# ESenseFE-Dual-TwinT-60HzNotchFilter-AdjQ.net
KiCad netlist of a schematic drawn in Altium Designer
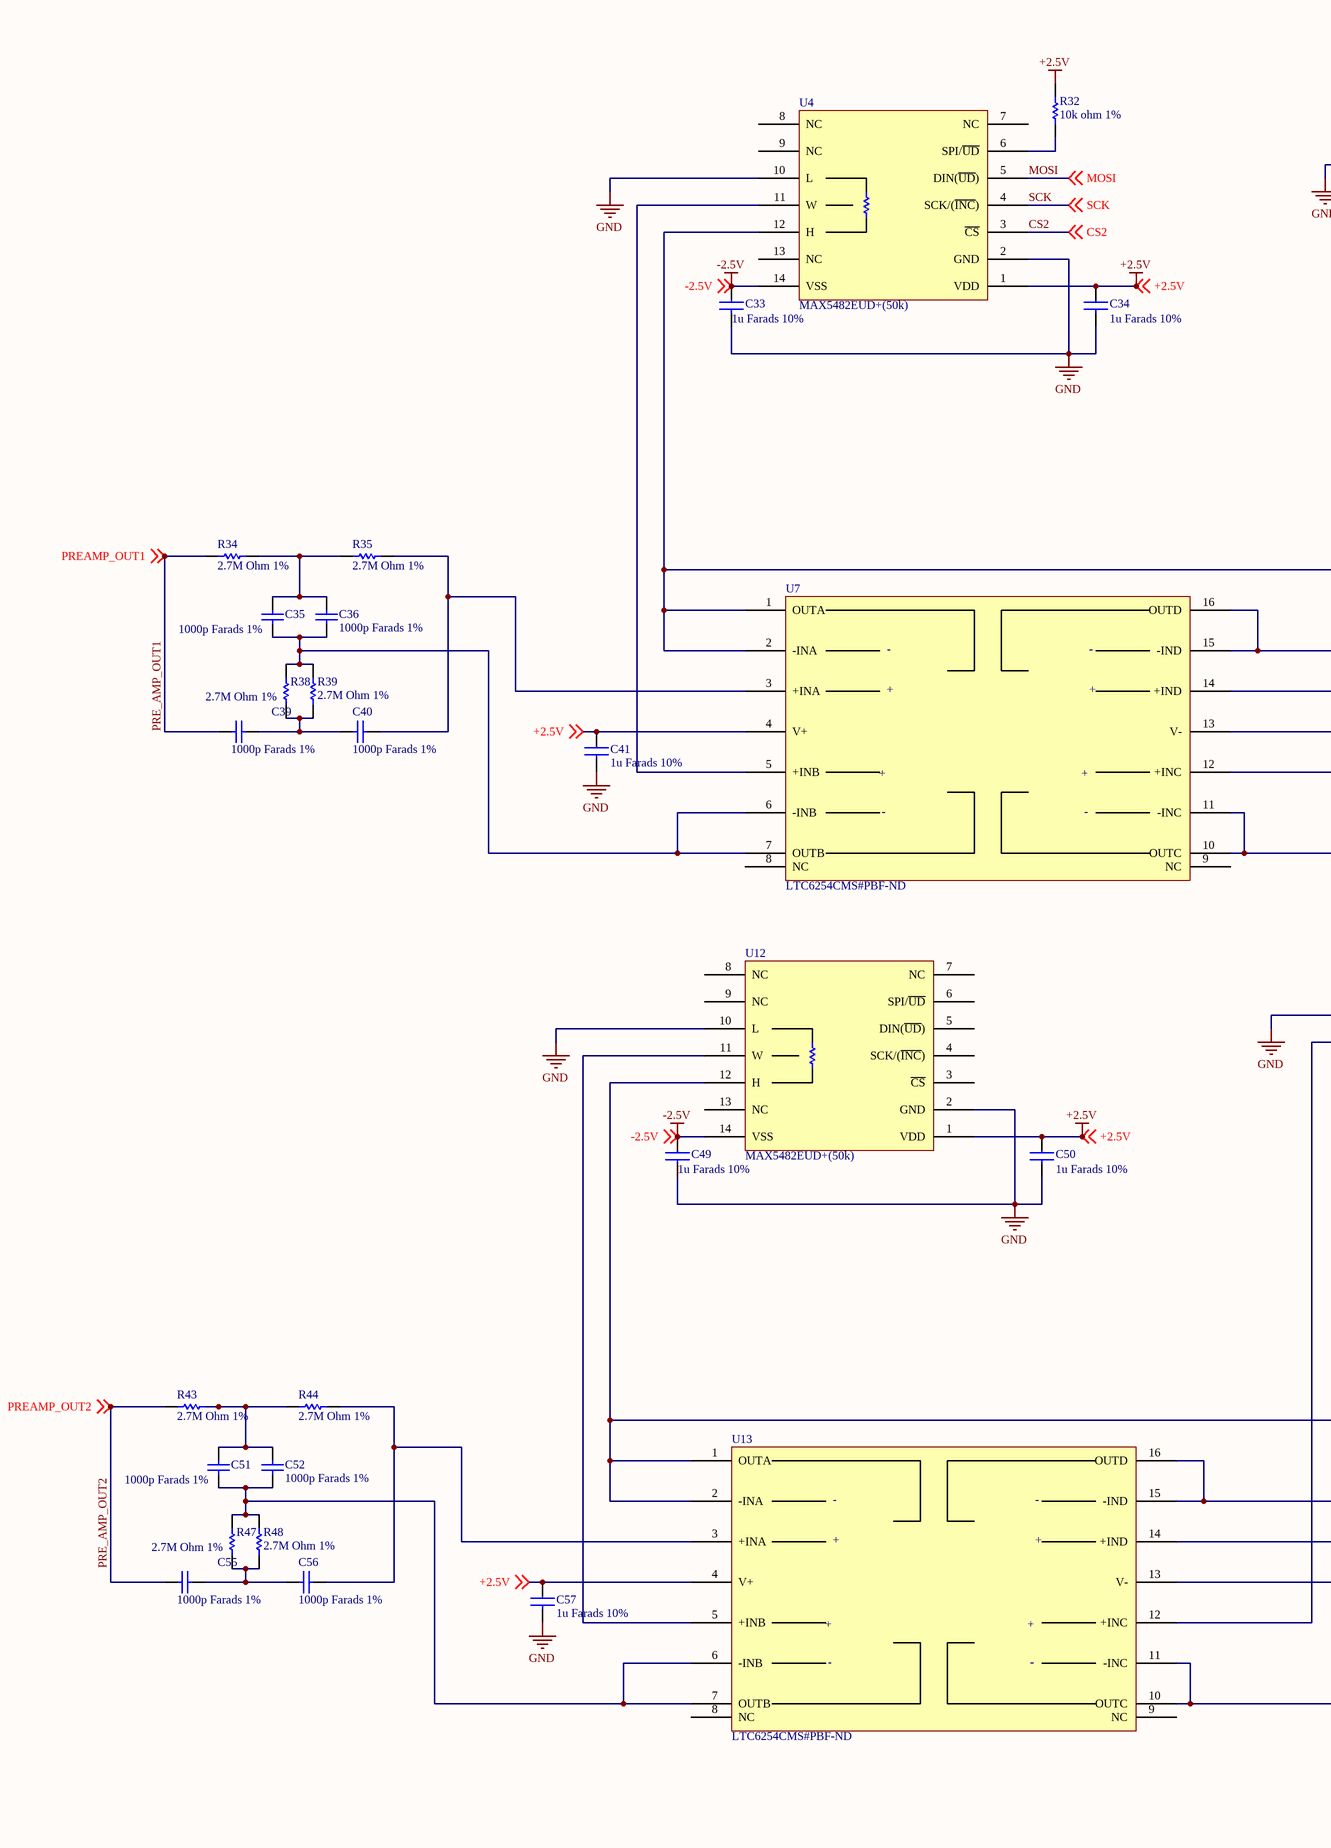
[diagram p0: ESenseFE-Dual-TwinT-60HzNotchFilter-AdjQ.SchDoc, left]
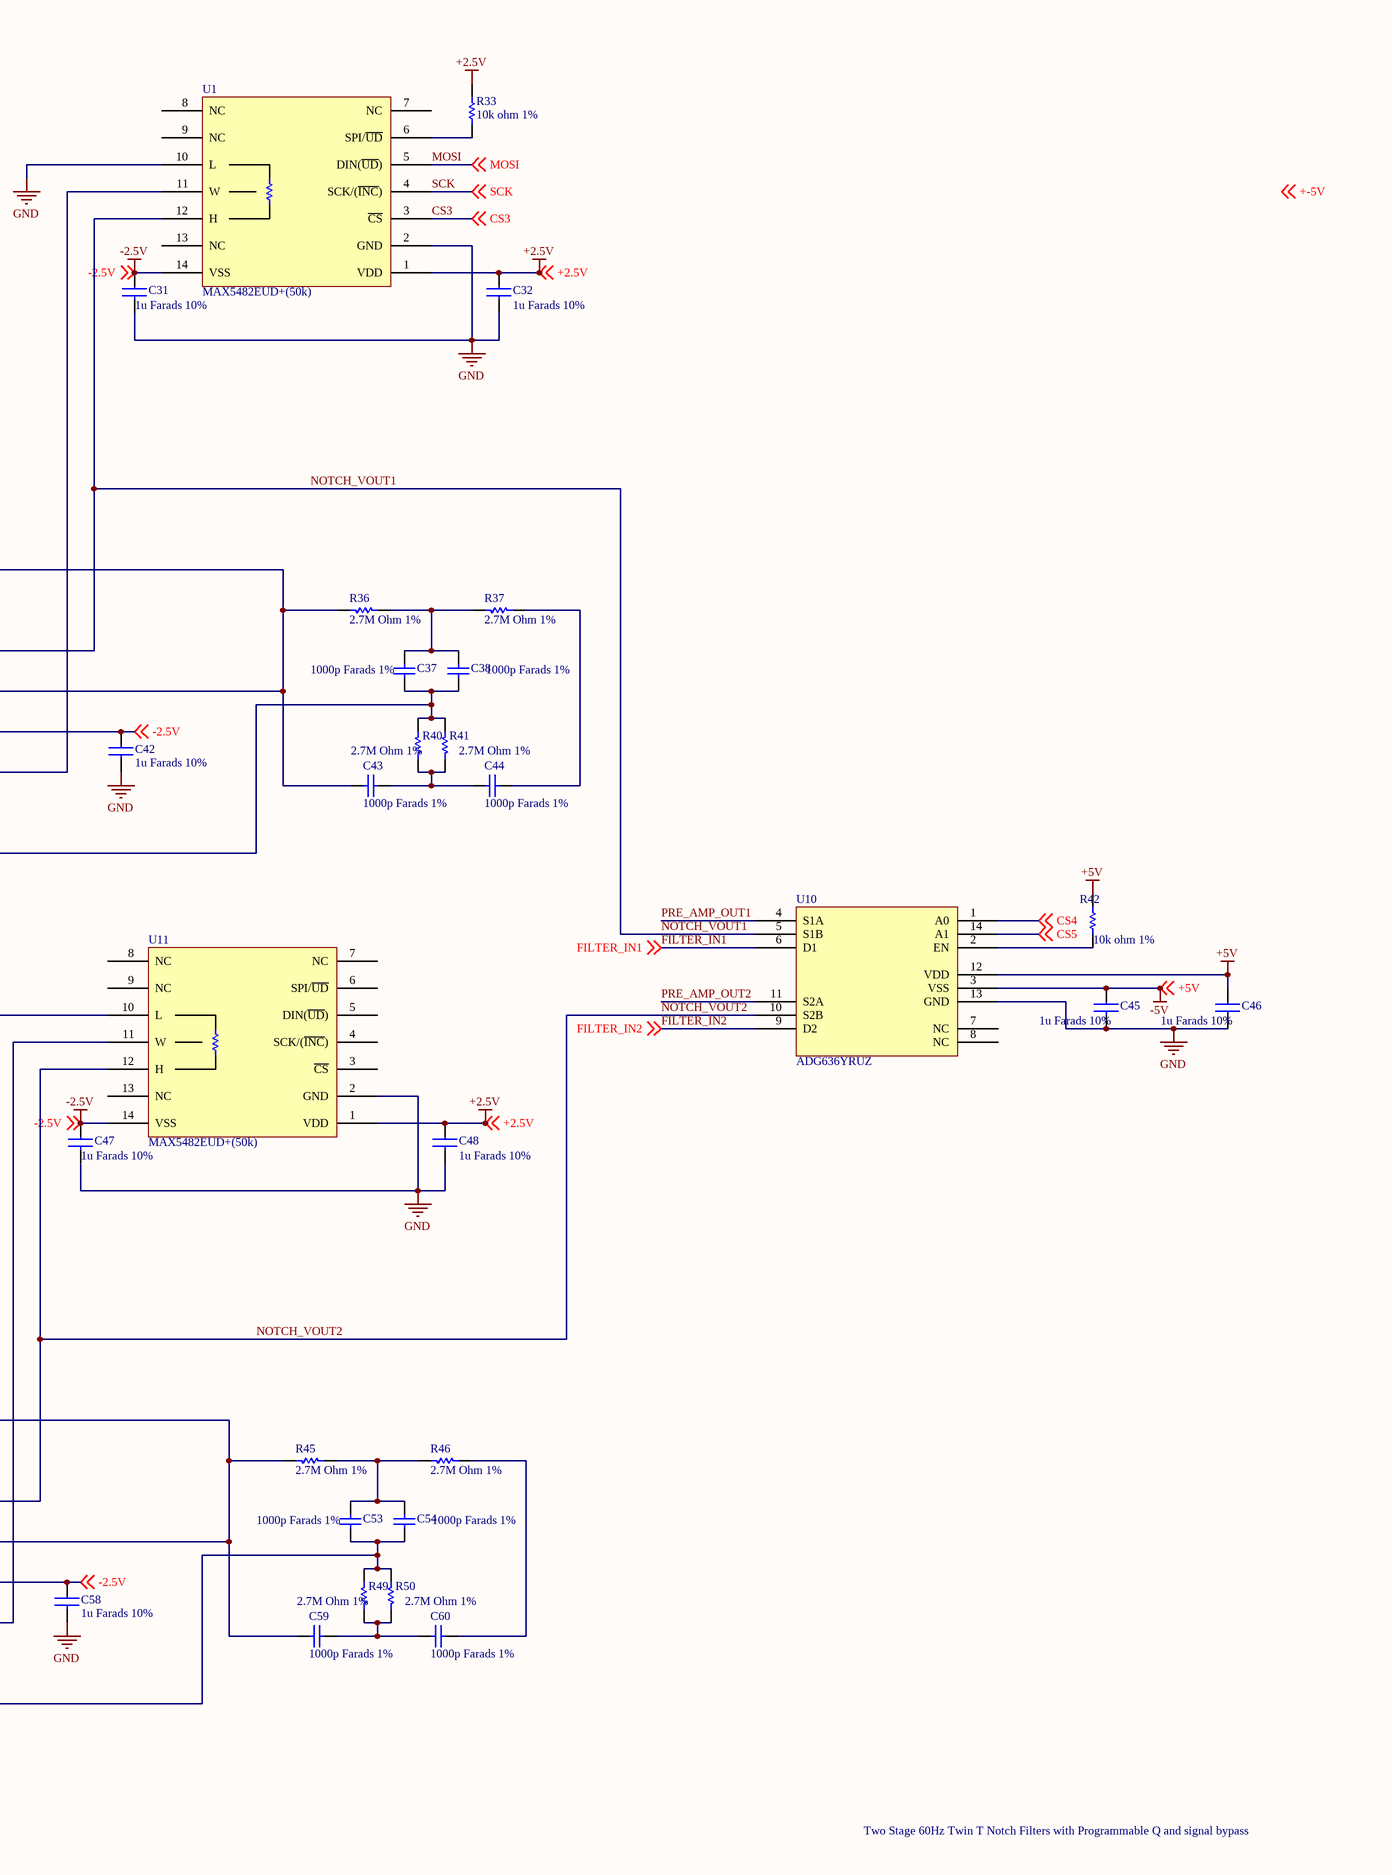
[diagram p1: ESenseFE-Dual-TwinT-60HzNotchFilter-AdjQ.SchDoc, right]

(export (version "E")
  (design (tool "Eeschema 10.0.6"))
  (components
    (comp (ref "C31")
      (value "1u Farads 10%")
      (footprint "SM/C_0603")
      (description "CAP CER 1.0UF 10V 10% X5R 0603")
      (fields (field (name "MFRPARTNUM") "GRM188R61A105KA61D"))
      (libsource (lib "FriedParts") (part "CAP NP"))
    )
    (comp (ref "C32")
      (value "1u Farads 10%")
      (footprint "SM/C_0603")
      (description "CAP CER 1.0UF 10V 10% X5R 0603")
      (fields (field (name "MFRPARTNUM") "GRM188R61A105KA61D"))
      (libsource (lib "FriedParts") (part "CAP NP"))
    )
    (comp (ref "C33")
      (value "1u Farads 10%")
      (footprint "SM/C_0603")
      (description "CAP CER 1.0UF 10V 10% X5R 0603")
      (fields (field (name "MFRPARTNUM") "GRM188R61A105KA61D"))
      (libsource (lib "FriedParts") (part "CAP NP"))
    )
    (comp (ref "C34")
      (value "1u Farads 10%")
      (footprint "SM/C_0603")
      (description "CAP CER 1.0UF 10V 10% X5R 0603")
      (fields (field (name "MFRPARTNUM") "GRM188R61A105KA61D"))
      (libsource (lib "FriedParts") (part "CAP NP"))
    )
    (comp (ref "C35")
      (value "1000p Farads 1%")
      (footprint "SM/C_0603")
      (description "capacitor ceramic 1000pf, 50v, c0g, 0603; dielectric")
      (fields (field (name "MFRPARTNUM") "06035A102FAT2A"))
      (libsource (lib "FriedParts") (part "CAP"))
    )
    (comp (ref "C36")
      (value "1000p Farads 1%")
      (footprint "SM/C_0603")
      (description "capacitor ceramic 1000pf, 50v, c0g, 0603; dielectric")
      (fields (field (name "MFRPARTNUM") "06035A102FAT2A"))
      (libsource (lib "FriedParts") (part "CAP"))
    )
    (comp (ref "C37")
      (value "1000p Farads 1%")
      (footprint "SM/C_0603")
      (description "capacitor ceramic 1000pf, 50v, c0g, 0603; dielectric")
      (fields (field (name "MFRPARTNUM") "06035A102FAT2A"))
      (libsource (lib "FriedParts") (part "CAP"))
    )
    (comp (ref "C38")
      (value "1000p Farads 1%")
      (footprint "SM/C_0603")
      (description "capacitor ceramic 1000pf, 50v, c0g, 0603; dielectric")
      (fields (field (name "MFRPARTNUM") "06035A102FAT2A"))
      (libsource (lib "FriedParts") (part "CAP"))
    )
    (comp (ref "C39")
      (value "1000p Farads 1%")
      (footprint "SM/C_0603")
      (description "capacitor ceramic 1000pf, 50v, c0g, 0603; dielectric")
      (fields (field (name "MFRPARTNUM") "06035A102FAT2A"))
      (libsource (lib "FriedParts") (part "CAP"))
    )
    (comp (ref "C40")
      (value "1000p Farads 1%")
      (footprint "SM/C_0603")
      (description "capacitor ceramic 1000pf, 50v, c0g, 0603; dielectric")
      (fields (field (name "MFRPARTNUM") "06035A102FAT2A"))
      (libsource (lib "FriedParts") (part "CAP"))
    )
    (comp (ref "C41")
      (value "1u Farads 10%")
      (footprint "SM/C_0603")
      (description "CAP CER 1.0UF 10V 10% X5R 0603")
      (fields (field (name "MFRPARTNUM") "GRM188R61A105KA61D"))
      (libsource (lib "FriedParts") (part "CAP NP"))
    )
    (comp (ref "C42")
      (value "1u Farads 10%")
      (footprint "SM/C_0603")
      (description "CAP CER 1.0UF 10V 10% X5R 0603")
      (fields (field (name "MFRPARTNUM") "GRM188R61A105KA61D"))
      (libsource (lib "FriedParts") (part "CAP NP"))
    )
    (comp (ref "C43")
      (value "1000p Farads 1%")
      (footprint "SM/C_0603")
      (description "capacitor ceramic 1000pf, 50v, c0g, 0603; dielectric")
      (fields (field (name "MFRPARTNUM") "06035A102FAT2A"))
      (libsource (lib "FriedParts") (part "CAP"))
    )
    (comp (ref "C44")
      (value "1000p Farads 1%")
      (footprint "SM/C_0603")
      (description "capacitor ceramic 1000pf, 50v, c0g, 0603; dielectric")
      (fields (field (name "MFRPARTNUM") "06035A102FAT2A"))
      (libsource (lib "FriedParts") (part "CAP"))
    )
    (comp (ref "C45")
      (value "1u Farads 10%")
      (footprint "SM/C_0603")
      (description "CAP CER 1.0UF 10V 10% X5R 0603")
      (fields (field (name "MFRPARTNUM") "GRM188R61A105KA61D"))
      (libsource (lib "FriedParts") (part "CAP NP"))
    )
    (comp (ref "C46")
      (value "1u Farads 10%")
      (footprint "SM/C_0603")
      (description "CAP CER 1.0UF 10V 10% X5R 0603")
      (fields (field (name "MFRPARTNUM") "GRM188R61A105KA61D"))
      (libsource (lib "FriedParts") (part "CAP NP"))
    )
    (comp (ref "C47")
      (value "1u Farads 10%")
      (footprint "SM/C_0603")
      (description "CAP CER 1.0UF 10V 10% X5R 0603")
      (fields (field (name "MFRPARTNUM") "GRM188R61A105KA61D"))
      (libsource (lib "FriedParts") (part "CAP NP"))
    )
    (comp (ref "C48")
      (value "1u Farads 10%")
      (footprint "SM/C_0603")
      (description "CAP CER 1.0UF 10V 10% X5R 0603")
      (fields (field (name "MFRPARTNUM") "GRM188R61A105KA61D"))
      (libsource (lib "FriedParts") (part "CAP NP"))
    )
    (comp (ref "C49")
      (value "1u Farads 10%")
      (footprint "SM/C_0603")
      (description "CAP CER 1.0UF 10V 10% X5R 0603")
      (fields (field (name "MFRPARTNUM") "GRM188R61A105KA61D"))
      (libsource (lib "FriedParts") (part "CAP NP"))
    )
    (comp (ref "C50")
      (value "1u Farads 10%")
      (footprint "SM/C_0603")
      (description "CAP CER 1.0UF 10V 10% X5R 0603")
      (fields (field (name "MFRPARTNUM") "GRM188R61A105KA61D"))
      (libsource (lib "FriedParts") (part "CAP NP"))
    )
    (comp (ref "C51")
      (value "1000p Farads 1%")
      (footprint "SM/C_0603")
      (description "capacitor ceramic 1000pf, 50v, c0g, 0603; dielectric")
      (fields (field (name "MFRPARTNUM") "06035A102FAT2A"))
      (libsource (lib "FriedParts") (part "CAP"))
    )
    (comp (ref "C52")
      (value "1000p Farads 1%")
      (footprint "SM/C_0603")
      (description "capacitor ceramic 1000pf, 50v, c0g, 0603; dielectric")
      (fields (field (name "MFRPARTNUM") "06035A102FAT2A"))
      (libsource (lib "FriedParts") (part "CAP"))
    )
    (comp (ref "C53")
      (value "1000p Farads 1%")
      (footprint "SM/C_0603")
      (description "capacitor ceramic 1000pf, 50v, c0g, 0603; dielectric")
      (fields (field (name "MFRPARTNUM") "06035A102FAT2A"))
      (libsource (lib "FriedParts") (part "CAP"))
    )
    (comp (ref "C54")
      (value "1000p Farads 1%")
      (footprint "SM/C_0603")
      (description "capacitor ceramic 1000pf, 50v, c0g, 0603; dielectric")
      (fields (field (name "MFRPARTNUM") "06035A102FAT2A"))
      (libsource (lib "FriedParts") (part "CAP"))
    )
    (comp (ref "C55")
      (value "1000p Farads 1%")
      (footprint "SM/C_0603")
      (description "capacitor ceramic 1000pf, 50v, c0g, 0603; dielectric")
      (fields (field (name "MFRPARTNUM") "06035A102FAT2A"))
      (libsource (lib "FriedParts") (part "CAP"))
    )
    (comp (ref "C56")
      (value "1000p Farads 1%")
      (footprint "SM/C_0603")
      (description "capacitor ceramic 1000pf, 50v, c0g, 0603; dielectric")
      (fields (field (name "MFRPARTNUM") "06035A102FAT2A"))
      (libsource (lib "FriedParts") (part "CAP"))
    )
    (comp (ref "C57")
      (value "1u Farads 10%")
      (footprint "SM/C_0603")
      (description "CAP CER 1.0UF 10V 10% X5R 0603")
      (fields (field (name "MFRPARTNUM") "GRM188R61A105KA61D"))
      (libsource (lib "FriedParts") (part "CAP NP"))
    )
    (comp (ref "C58")
      (value "1u Farads 10%")
      (footprint "SM/C_0603")
      (description "CAP CER 1.0UF 10V 10% X5R 0603")
      (fields (field (name "MFRPARTNUM") "GRM188R61A105KA61D"))
      (libsource (lib "FriedParts") (part "CAP NP"))
    )
    (comp (ref "C59")
      (value "1000p Farads 1%")
      (footprint "SM/C_0603")
      (description "capacitor ceramic 1000pf, 50v, c0g, 0603; dielectric")
      (fields (field (name "MFRPARTNUM") "06035A102FAT2A"))
      (libsource (lib "FriedParts") (part "CAP"))
    )
    (comp (ref "C60")
      (value "1000p Farads 1%")
      (footprint "SM/C_0603")
      (description "capacitor ceramic 1000pf, 50v, c0g, 0603; dielectric")
      (fields (field (name "MFRPARTNUM") "06035A102FAT2A"))
      (libsource (lib "FriedParts") (part "CAP"))
    )
    (comp (ref "R32")
      (value "10k ohm 1%")
      (footprint "SM/C_0603")
      (description "resistor, 0603, 0.1w, 1%, 10k; resistance:10kohm; resistance")
      (fields (field (name "MFRPARTNUM") "ERJ-3EKF1002V") (field (name "PUBLISHER") "Altium Limited"))
      (libsource (lib "FriedParts") (part "Res1"))
    )
    (comp (ref "R33")
      (value "10k ohm 1%")
      (footprint "SM/C_0603")
      (description "resistor, 0603, 0.1w, 1%, 10k; resistance:10kohm; resistance")
      (fields (field (name "MFRPARTNUM") "ERJ-3EKF1002V") (field (name "PUBLISHER") "Altium Limited"))
      (libsource (lib "FriedParts") (part "Res1"))
    )
    (comp (ref "R34")
      (value "2.7M Ohm 1%")
      (footprint "SM/R_0603")
      (description "res, thick film, 2.7mohm, 100mw, 1%; resistance:2.7mohm;")
      (fields (field (name "MFRPARTNUM") "CRCW06032M70FKEA") (field (name "PUBLISHER") "Altium Limited"))
      (libsource (lib "FriedParts") (part "Res1"))
    )
    (comp (ref "R35")
      (value "2.7M Ohm 1%")
      (footprint "SM/R_0603")
      (description "res, thick film, 2.7mohm, 100mw, 1%; resistance:2.7mohm;")
      (fields (field (name "MFRPARTNUM") "CRCW06032M70FKEA") (field (name "PUBLISHER") "Altium Limited"))
      (libsource (lib "FriedParts") (part "Res1"))
    )
    (comp (ref "R36")
      (value "2.7M Ohm 1%")
      (footprint "SM/R_0603")
      (description "res, thick film, 2.7mohm, 100mw, 1%; resistance:2.7mohm;")
      (fields (field (name "MFRPARTNUM") "CRCW06032M70FKEA") (field (name "PUBLISHER") "Altium Limited"))
      (libsource (lib "FriedParts") (part "Res1"))
    )
    (comp (ref "R37")
      (value "2.7M Ohm 1%")
      (footprint "SM/R_0603")
      (description "res, thick film, 2.7mohm, 100mw, 1%; resistance:2.7mohm;")
      (fields (field (name "MFRPARTNUM") "CRCW06032M70FKEA") (field (name "PUBLISHER") "Altium Limited"))
      (libsource (lib "FriedParts") (part "Res1"))
    )
    (comp (ref "R38")
      (value "2.7M Ohm 1%")
      (footprint "SM/R_0603")
      (description "res, thick film, 2.7mohm, 100mw, 1%; resistance:2.7mohm;")
      (fields (field (name "MFRPARTNUM") "CRCW06032M70FKEA") (field (name "PUBLISHER") "Altium Limited"))
      (libsource (lib "FriedParts") (part "Res1"))
    )
    (comp (ref "R39")
      (value "2.7M Ohm 1%")
      (footprint "SM/R_0603")
      (description "res, thick film, 2.7mohm, 100mw, 1%; resistance:2.7mohm;")
      (fields (field (name "MFRPARTNUM") "CRCW06032M70FKEA") (field (name "PUBLISHER") "Altium Limited"))
      (libsource (lib "FriedParts") (part "Res1"))
    )
    (comp (ref "R40")
      (value "2.7M Ohm 1%")
      (footprint "SM/R_0603")
      (description "res, thick film, 2.7mohm, 100mw, 1%; resistance:2.7mohm;")
      (fields (field (name "MFRPARTNUM") "CRCW06032M70FKEA") (field (name "PUBLISHER") "Altium Limited"))
      (libsource (lib "FriedParts") (part "Res1"))
    )
    (comp (ref "R41")
      (value "2.7M Ohm 1%")
      (footprint "SM/R_0603")
      (description "res, thick film, 2.7mohm, 100mw, 1%; resistance:2.7mohm;")
      (fields (field (name "MFRPARTNUM") "CRCW06032M70FKEA") (field (name "PUBLISHER") "Altium Limited"))
      (libsource (lib "FriedParts") (part "Res1"))
    )
    (comp (ref "R42")
      (value "10k ohm 1%")
      (footprint "SM/C_0603")
      (description "resistor, 0603, 0.1w, 1%, 10k; resistance:10kohm; resistance")
      (fields (field (name "MFRPARTNUM") "ERJ-3EKF1002V") (field (name "PUBLISHER") "Altium Limited"))
      (libsource (lib "FriedParts") (part "Res1"))
    )
    (comp (ref "R43")
      (value "2.7M Ohm 1%")
      (footprint "SM/R_0603")
      (description "res, thick film, 2.7mohm, 100mw, 1%; resistance:2.7mohm;")
      (fields (field (name "MFRPARTNUM") "CRCW06032M70FKEA") (field (name "PUBLISHER") "Altium Limited"))
      (libsource (lib "FriedParts") (part "Res1"))
    )
    (comp (ref "R44")
      (value "2.7M Ohm 1%")
      (footprint "SM/R_0603")
      (description "res, thick film, 2.7mohm, 100mw, 1%; resistance:2.7mohm;")
      (fields (field (name "MFRPARTNUM") "CRCW06032M70FKEA") (field (name "PUBLISHER") "Altium Limited"))
      (libsource (lib "FriedParts") (part "Res1"))
    )
    (comp (ref "R45")
      (value "2.7M Ohm 1%")
      (footprint "SM/R_0603")
      (description "res, thick film, 2.7mohm, 100mw, 1%; resistance:2.7mohm;")
      (fields (field (name "MFRPARTNUM") "CRCW06032M70FKEA") (field (name "PUBLISHER") "Altium Limited"))
      (libsource (lib "FriedParts") (part "Res1"))
    )
    (comp (ref "R46")
      (value "2.7M Ohm 1%")
      (footprint "SM/R_0603")
      (description "res, thick film, 2.7mohm, 100mw, 1%; resistance:2.7mohm;")
      (fields (field (name "MFRPARTNUM") "CRCW06032M70FKEA") (field (name "PUBLISHER") "Altium Limited"))
      (libsource (lib "FriedParts") (part "Res1"))
    )
    (comp (ref "R47")
      (value "2.7M Ohm 1%")
      (footprint "SM/R_0603")
      (description "res, thick film, 2.7mohm, 100mw, 1%; resistance:2.7mohm;")
      (fields (field (name "MFRPARTNUM") "CRCW06032M70FKEA") (field (name "PUBLISHER") "Altium Limited"))
      (libsource (lib "FriedParts") (part "Res1"))
    )
    (comp (ref "R48")
      (value "2.7M Ohm 1%")
      (footprint "SM/R_0603")
      (description "res, thick film, 2.7mohm, 100mw, 1%; resistance:2.7mohm;")
      (fields (field (name "MFRPARTNUM") "CRCW06032M70FKEA") (field (name "PUBLISHER") "Altium Limited"))
      (libsource (lib "FriedParts") (part "Res1"))
    )
    (comp (ref "R49")
      (value "2.7M Ohm 1%")
      (footprint "SM/R_0603")
      (description "res, thick film, 2.7mohm, 100mw, 1%; resistance:2.7mohm;")
      (fields (field (name "MFRPARTNUM") "CRCW06032M70FKEA") (field (name "PUBLISHER") "Altium Limited"))
      (libsource (lib "FriedParts") (part "Res1"))
    )
    (comp (ref "R50")
      (value "2.7M Ohm 1%")
      (footprint "SM/R_0603")
      (description "res, thick film, 2.7mohm, 100mw, 1%; resistance:2.7mohm;")
      (fields (field (name "MFRPARTNUM") "CRCW06032M70FKEA") (field (name "PUBLISHER") "Altium Limited"))
      (libsource (lib "FriedParts") (part "Res1"))
    )
    (comp (ref "U1")
      (value "MAX5482EUD+(50k)")
      (footprint "TSSOP-16Lead-MAX548X")
      (description "dpot, nv, linear taper, 10 bit, smd; resistance range")
      (fields (field (name "MFRPARTNUM") "MAX5482EUD+(1)"))
      (libsource (lib "FriedParts") (part "MAX5482"))
    )
    (comp (ref "U4")
      (value "MAX5482EUD+(50k)")
      (footprint "TSSOP-16Lead-MAX548X")
      (description "dpot, nv, linear taper, 10 bit, smd; resistance range")
      (fields (field (name "MFRPARTNUM") "MAX5482EUD+(1)"))
      (libsource (lib "FriedParts") (part "MAX5482"))
    )
    (comp (ref "U7")
      (value "LTC6254CMS#PBF-ND")
      (footprint "MSOP-16Lead-LTC6254")
      (description "op amp, dual, r-r, 180mhz, 8msop; op amp type:unity gain")
      (libsource (lib "FriedParts") (part "LTC6254"))
    )
    (comp (ref "U10")
      (value "ADG636YRUZ")
      (footprint "TSSOP-14Lead-AnalogDevices-ADG636")
      (description "switch, spdt dual, tssop14, 636; switch type, analogue:spdt;")
      (libsource (lib "FriedParts") (part "ADG636"))
    )
    (comp (ref "U11")
      (value "MAX5482EUD+(50k)")
      (footprint "TSSOP-16Lead-MAX548X")
      (description "dpot, nv, linear taper, 10 bit, smd; resistance range")
      (fields (field (name "MFRPARTNUM") "MAX5482EUD+(1)"))
      (libsource (lib "FriedParts") (part "MAX5482"))
    )
    (comp (ref "U12")
      (value "MAX5482EUD+(50k)")
      (footprint "TSSOP-16Lead-MAX548X")
      (description "dpot, nv, linear taper, 10 bit, smd; resistance range")
      (fields (field (name "MFRPARTNUM") "MAX5482EUD+(1)"))
      (libsource (lib "FriedParts") (part "MAX5482"))
    )
    (comp (ref "U13")
      (value "LTC6254CMS#PBF-ND")
      (footprint "MSOP-16Lead-LTC6254")
      (description "op amp, dual, r-r, 180mhz, 8msop; op amp type:unity gain")
      (libsource (lib "FriedParts") (part "LTC6254"))
    )
  )
  (nets
    (net (code "2") (name "+2.5V") (class "Default")
      (node (ref "C32") (pin "1") (pinfunction "1_1") (pintype "passive"))
      (node (ref "C34") (pin "1") (pinfunction "1_1") (pintype "passive"))
      (node (ref "C41") (pin "1") (pinfunction "1_1") (pintype "passive"))
      (node (ref "C48") (pin "1") (pinfunction "1_1") (pintype "passive"))
      (node (ref "C50") (pin "1") (pinfunction "1_1") (pintype "passive"))
      (node (ref "C57") (pin "1") (pinfunction "1_1") (pintype "passive"))
      (node (ref "R32") (pin "2") (pinfunction "2_2") (pintype "passive"))
      (node (ref "R33") (pin "2") (pinfunction "2_2") (pintype "passive"))
      (node (ref "U1") (pin "1") (pinfunction "VDD_1") (pintype "passive"))
      (node (ref "U11") (pin "1") (pinfunction "VDD_1") (pintype "passive"))
      (node (ref "U12") (pin "1") (pinfunction "VDD_1") (pintype "passive"))
      (node (ref "U13") (pin "4") (pinfunction "V+_4") (pintype "passive"))
      (node (ref "U4") (pin "1") (pinfunction "VDD_1") (pintype "passive"))
      (node (ref "U7") (pin "4") (pinfunction "V+_4") (pintype "passive"))
    )
    (net (code "3") (name "+5V") (class "Default")
      (node (ref "C45") (pin "1") (pinfunction "1_1") (pintype "passive"))
      (node (ref "C46") (pin "1") (pinfunction "1_1") (pintype "passive"))
      (node (ref "R42") (pin "1") (pinfunction "1_1") (pintype "passive"))
      (node (ref "U10") (pin "12") (pinfunction "VDD_12") (pintype "passive"))
      (node (ref "U10") (pin "3") (pinfunction "VSS_3") (pintype "passive"))
    )
    (net (code "4") (name "-2.5V") (class "Default")
      (node (ref "C31") (pin "1") (pinfunction "1_1") (pintype "passive"))
      (node (ref "C33") (pin "1") (pinfunction "1_1") (pintype "passive"))
      (node (ref "C42") (pin "1") (pinfunction "1_1") (pintype "passive"))
      (node (ref "C47") (pin "1") (pinfunction "1_1") (pintype "passive"))
      (node (ref "C49") (pin "1") (pinfunction "1_1") (pintype "passive"))
      (node (ref "C58") (pin "1") (pinfunction "1_1") (pintype "passive"))
      (node (ref "U1") (pin "14") (pinfunction "VSS_14") (pintype "passive"))
      (node (ref "U11") (pin "14") (pinfunction "VSS_14") (pintype "passive"))
      (node (ref "U12") (pin "14") (pinfunction "VSS_14") (pintype "passive"))
      (node (ref "U13") (pin "13") (pinfunction "V-_13") (pintype "passive"))
      (node (ref "U4") (pin "14") (pinfunction "VSS_14") (pintype "passive"))
      (node (ref "U7") (pin "13") (pinfunction "V-_13") (pintype "passive"))
    )
    (net (code "5") (name "/NOTCH_VOUT1") (class "Default")
      (node (ref "U1") (pin "12") (pinfunction "H_12") (pintype "passive"))
      (node (ref "U10") (pin "5") (pinfunction "S1B_5") (pintype "passive"))
      (node (ref "U7") (pin "15") (pinfunction "-IND_15") (pintype "passive"))
      (node (ref "U7") (pin "16") (pinfunction "OUTD_16") (pintype "passive"))
    )
    (net (code "6") (name "/NOTCH_VOUT2") (class "Default")
      (node (ref "U10") (pin "10") (pinfunction "S2B_10") (pintype "passive"))
      (node (ref "U11") (pin "12") (pinfunction "H_12") (pintype "passive"))
      (node (ref "U13") (pin "15") (pinfunction "-IND_15") (pintype "passive"))
      (node (ref "U13") (pin "16") (pinfunction "OUTD_16") (pintype "passive"))
    )
    (net (code "7") (name "CS2") (class "Default")
      (node (ref "U4") (pin "3") (pinfunction "~{CS}_3") (pintype "passive"))
    )
    (net (code "8") (name "CS3") (class "Default")
      (node (ref "U1") (pin "3") (pinfunction "~{CS}_3") (pintype "passive"))
    )
    (net (code "9") (name "CS4") (class "Default")
      (node (ref "U10") (pin "1") (pinfunction "A0_1") (pintype "passive"))
    )
    (net (code "10") (name "CS5") (class "Default")
      (node (ref "U10") (pin "14") (pinfunction "A1_14") (pintype "passive"))
    )
    (net (code "11") (name "FILTER_IN1") (class "Default")
      (node (ref "U10") (pin "6") (pinfunction "D1_6") (pintype "passive"))
    )
    (net (code "12") (name "FILTER_IN2") (class "Default")
      (node (ref "U10") (pin "9") (pinfunction "D2_9") (pintype "passive"))
    )
    (net (code "13") (name "GND") (class "Default")
      (node (ref "C31") (pin "2") (pinfunction "2_2") (pintype "passive"))
      (node (ref "C32") (pin "2") (pinfunction "2_2") (pintype "passive"))
      (node (ref "C33") (pin "2") (pinfunction "2_2") (pintype "passive"))
      (node (ref "C34") (pin "2") (pinfunction "2_2") (pintype "passive"))
      (node (ref "C41") (pin "2") (pinfunction "2_2") (pintype "passive"))
      (node (ref "C42") (pin "2") (pinfunction "2_2") (pintype "passive"))
      (node (ref "C45") (pin "2") (pinfunction "2_2") (pintype "passive"))
      (node (ref "C46") (pin "2") (pinfunction "2_2") (pintype "passive"))
      (node (ref "C47") (pin "2") (pinfunction "2_2") (pintype "passive"))
      (node (ref "C48") (pin "2") (pinfunction "2_2") (pintype "passive"))
      (node (ref "C49") (pin "2") (pinfunction "2_2") (pintype "passive"))
      (node (ref "C50") (pin "2") (pinfunction "2_2") (pintype "passive"))
      (node (ref "C57") (pin "2") (pinfunction "2_2") (pintype "passive"))
      (node (ref "C58") (pin "2") (pinfunction "2_2") (pintype "passive"))
      (node (ref "U1") (pin "10") (pinfunction "L_10") (pintype "passive"))
      (node (ref "U1") (pin "2") (pinfunction "GND_2") (pintype "passive"))
      (node (ref "U10") (pin "13") (pinfunction "GND_13") (pintype "passive"))
      (node (ref "U11") (pin "10") (pinfunction "L_10") (pintype "passive"))
      (node (ref "U11") (pin "2") (pinfunction "GND_2") (pintype "passive"))
      (node (ref "U12") (pin "10") (pinfunction "L_10") (pintype "passive"))
      (node (ref "U12") (pin "2") (pinfunction "GND_2") (pintype "passive"))
      (node (ref "U4") (pin "10") (pinfunction "L_10") (pintype "passive"))
      (node (ref "U4") (pin "2") (pinfunction "GND_2") (pintype "passive"))
    )
    (net (code "14") (name "MOSI") (class "Default")
      (node (ref "U1") (pin "5") (pinfunction "DIN(~{UD})_5") (pintype "passive"))
      (node (ref "U4") (pin "5") (pinfunction "DIN(~{UD})_5") (pintype "passive"))
    )
    (net (code "15") (name "Net-(C35-Pad2)") (class "Default")
      (node (ref "C35") (pin "2") (pinfunction "2_2") (pintype "passive"))
      (node (ref "C36") (pin "2") (pinfunction "2_2") (pintype "passive"))
      (node (ref "R34") (pin "2") (pinfunction "2_2") (pintype "passive"))
      (node (ref "R35") (pin "1") (pinfunction "1_1") (pintype "passive"))
    )
    (net (code "16") (name "Net-(C37-Pad2)") (class "Default")
      (node (ref "C37") (pin "2") (pinfunction "2_2") (pintype "passive"))
      (node (ref "C38") (pin "2") (pinfunction "2_2") (pintype "passive"))
      (node (ref "R36") (pin "1") (pinfunction "1_1") (pintype "passive"))
      (node (ref "R37") (pin "2") (pinfunction "2_2") (pintype "passive"))
    )
    (net (code "17") (name "Net-(C39-Pad1)") (class "Default")
      (node (ref "C39") (pin "1") (pinfunction "1_1") (pintype "passive"))
      (node (ref "C40") (pin "2") (pinfunction "2_2") (pintype "passive"))
      (node (ref "R38") (pin "2") (pinfunction "2_2") (pintype "passive"))
      (node (ref "R39") (pin "2") (pinfunction "2_2") (pintype "passive"))
    )
    (net (code "18") (name "Net-(C43-Pad2)") (class "Default")
      (node (ref "C43") (pin "2") (pinfunction "2_2") (pintype "passive"))
      (node (ref "C44") (pin "1") (pinfunction "1_1") (pintype "passive"))
      (node (ref "R40") (pin "2") (pinfunction "2_2") (pintype "passive"))
      (node (ref "R41") (pin "2") (pinfunction "2_2") (pintype "passive"))
    )
    (net (code "19") (name "Net-(C44-Pad2)") (class "Default")
      (node (ref "C44") (pin "2") (pinfunction "2_2") (pintype "passive"))
      (node (ref "R37") (pin "1") (pinfunction "1_1") (pintype "passive"))
    )
    (net (code "20") (name "Net-(C51-Pad2)") (class "Default")
      (node (ref "C51") (pin "2") (pinfunction "2_2") (pintype "passive"))
      (node (ref "C52") (pin "2") (pinfunction "2_2") (pintype "passive"))
      (node (ref "R43") (pin "2") (pinfunction "2_2") (pintype "passive"))
      (node (ref "R44") (pin "1") (pinfunction "1_1") (pintype "passive"))
    )
    (net (code "21") (name "Net-(C53-Pad2)") (class "Default")
      (node (ref "C53") (pin "2") (pinfunction "2_2") (pintype "passive"))
      (node (ref "C54") (pin "2") (pinfunction "2_2") (pintype "passive"))
      (node (ref "R45") (pin "1") (pinfunction "1_1") (pintype "passive"))
      (node (ref "R46") (pin "2") (pinfunction "2_2") (pintype "passive"))
    )
    (net (code "22") (name "Net-(C55-Pad1)") (class "Default")
      (node (ref "C55") (pin "1") (pinfunction "1_1") (pintype "passive"))
      (node (ref "C56") (pin "2") (pinfunction "2_2") (pintype "passive"))
      (node (ref "R47") (pin "2") (pinfunction "2_2") (pintype "passive"))
      (node (ref "R48") (pin "2") (pinfunction "2_2") (pintype "passive"))
    )
    (net (code "23") (name "Net-(C59-Pad2)") (class "Default")
      (node (ref "C59") (pin "2") (pinfunction "2_2") (pintype "passive"))
      (node (ref "C60") (pin "1") (pinfunction "1_1") (pintype "passive"))
      (node (ref "R49") (pin "2") (pinfunction "2_2") (pintype "passive"))
      (node (ref "R50") (pin "2") (pinfunction "2_2") (pintype "passive"))
    )
    (net (code "24") (name "Net-(C60-Pad2)") (class "Default")
      (node (ref "C60") (pin "2") (pinfunction "2_2") (pintype "passive"))
      (node (ref "R46") (pin "1") (pinfunction "1_1") (pintype "passive"))
    )
    (net (code "25") (name "Net-(U1-SPI{slash}~{UD})") (class "Default")
      (node (ref "R33") (pin "1") (pinfunction "1_1") (pintype "passive"))
      (node (ref "U1") (pin "6") (pinfunction "SPI/~{UD}_6") (pintype "passive"))
    )
    (net (code "26") (name "Net-(U1-W)") (class "Default")
      (node (ref "U1") (pin "11") (pinfunction "W_11") (pintype "passive"))
      (node (ref "U7") (pin "12") (pinfunction "+INC_12") (pintype "passive"))
    )
    (net (code "27") (name "Net-(U4-H)") (class "Default")
      (node (ref "C43") (pin "1") (pinfunction "1_1") (pintype "passive"))
      (node (ref "R36") (pin "2") (pinfunction "2_2") (pintype "passive"))
      (node (ref "U4") (pin "12") (pinfunction "H_12") (pintype "passive"))
      (node (ref "U7") (pin "1") (pinfunction "OUTA_1") (pintype "passive"))
      (node (ref "U7") (pin "14") (pinfunction "+IND_14") (pintype "passive"))
      (node (ref "U7") (pin "2") (pinfunction "-INA_2") (pintype "passive"))
    )
    (net (code "28") (name "Net-(U4-SPI{slash}~{UD})") (class "Default")
      (node (ref "R32") (pin "1") (pinfunction "1_1") (pintype "passive"))
      (node (ref "U4") (pin "6") (pinfunction "SPI/~{UD}_6") (pintype "passive"))
    )
    (net (code "29") (name "Net-(U4-W)") (class "Default")
      (node (ref "U4") (pin "11") (pinfunction "W_11") (pintype "passive"))
      (node (ref "U7") (pin "5") (pinfunction "+INB_5") (pintype "passive"))
    )
    (net (code "30") (name "Net-(U7-+INA)") (class "Default")
      (node (ref "C40") (pin "1") (pinfunction "1_1") (pintype "passive"))
      (node (ref "R35") (pin "2") (pinfunction "2_2") (pintype "passive"))
      (node (ref "U7") (pin "3") (pinfunction "+INA_3") (pintype "passive"))
    )
    (net (code "31") (name "Net-(U7--INB)") (class "Default")
      (node (ref "C35") (pin "1") (pinfunction "1_1") (pintype "passive"))
      (node (ref "C36") (pin "1") (pinfunction "1_1") (pintype "passive"))
      (node (ref "R38") (pin "1") (pinfunction "1_1") (pintype "passive"))
      (node (ref "R39") (pin "1") (pinfunction "1_1") (pintype "passive"))
      (node (ref "U7") (pin "6") (pinfunction "-INB_6") (pintype "passive"))
      (node (ref "U7") (pin "7") (pinfunction "OUTB_7") (pintype "passive"))
    )
    (net (code "32") (name "Net-(U7--INC)") (class "Default")
      (node (ref "C37") (pin "1") (pinfunction "1_1") (pintype "passive"))
      (node (ref "C38") (pin "1") (pinfunction "1_1") (pintype "passive"))
      (node (ref "R40") (pin "1") (pinfunction "1_1") (pintype "passive"))
      (node (ref "R41") (pin "1") (pinfunction "1_1") (pintype "passive"))
      (node (ref "U7") (pin "10") (pinfunction "OUTC_10") (pintype "passive"))
      (node (ref "U7") (pin "11") (pinfunction "-INC_11") (pintype "passive"))
    )
    (net (code "33") (name "Net-(U10-EN)") (class "Default")
      (node (ref "R42") (pin "2") (pinfunction "2_2") (pintype "passive"))
      (node (ref "U10") (pin "2") (pinfunction "EN_2") (pintype "passive"))
    )
    (net (code "34") (name "Net-(U11-W)") (class "Default")
      (node (ref "U11") (pin "11") (pinfunction "W_11") (pintype "passive"))
      (node (ref "U13") (pin "12") (pinfunction "+INC_12") (pintype "passive"))
    )
    (net (code "35") (name "Net-(U12-H)") (class "Default")
      (node (ref "C59") (pin "1") (pinfunction "1_1") (pintype "passive"))
      (node (ref "R45") (pin "2") (pinfunction "2_2") (pintype "passive"))
      (node (ref "U12") (pin "12") (pinfunction "H_12") (pintype "passive"))
      (node (ref "U13") (pin "1") (pinfunction "OUTA_1") (pintype "passive"))
      (node (ref "U13") (pin "14") (pinfunction "+IND_14") (pintype "passive"))
      (node (ref "U13") (pin "2") (pinfunction "-INA_2") (pintype "passive"))
    )
    (net (code "36") (name "Net-(U12-W)") (class "Default")
      (node (ref "U12") (pin "11") (pinfunction "W_11") (pintype "passive"))
      (node (ref "U13") (pin "5") (pinfunction "+INB_5") (pintype "passive"))
    )
    (net (code "37") (name "Net-(U13-+INA)") (class "Default")
      (node (ref "C56") (pin "1") (pinfunction "1_1") (pintype "passive"))
      (node (ref "R44") (pin "2") (pinfunction "2_2") (pintype "passive"))
      (node (ref "U13") (pin "3") (pinfunction "+INA_3") (pintype "passive"))
    )
    (net (code "38") (name "Net-(U13--INB)") (class "Default")
      (node (ref "C51") (pin "1") (pinfunction "1_1") (pintype "passive"))
      (node (ref "C52") (pin "1") (pinfunction "1_1") (pintype "passive"))
      (node (ref "R47") (pin "1") (pinfunction "1_1") (pintype "passive"))
      (node (ref "R48") (pin "1") (pinfunction "1_1") (pintype "passive"))
      (node (ref "U13") (pin "6") (pinfunction "-INB_6") (pintype "passive"))
      (node (ref "U13") (pin "7") (pinfunction "OUTB_7") (pintype "passive"))
    )
    (net (code "39") (name "Net-(U13--INC)") (class "Default")
      (node (ref "C53") (pin "1") (pinfunction "1_1") (pintype "passive"))
      (node (ref "C54") (pin "1") (pinfunction "1_1") (pintype "passive"))
      (node (ref "R49") (pin "1") (pinfunction "1_1") (pintype "passive"))
      (node (ref "R50") (pin "1") (pinfunction "1_1") (pintype "passive"))
      (node (ref "U13") (pin "10") (pinfunction "OUTC_10") (pintype "passive"))
      (node (ref "U13") (pin "11") (pinfunction "-INC_11") (pintype "passive"))
    )
    (net (code "40") (name "PREAMP_OUT1") (class "Default")
      (node (ref "C39") (pin "2") (pinfunction "2_2") (pintype "passive"))
      (node (ref "R34") (pin "1") (pinfunction "1_1") (pintype "passive"))
      (node (ref "U10") (pin "4") (pinfunction "S1A_4") (pintype "passive"))
    )
    (net (code "41") (name "PREAMP_OUT2") (class "Default")
      (node (ref "C55") (pin "2") (pinfunction "2_2") (pintype "passive"))
      (node (ref "R43") (pin "1") (pinfunction "1_1") (pintype "passive"))
      (node (ref "U10") (pin "11") (pinfunction "S2A_11") (pintype "passive"))
    )
    (net (code "42") (name "SCK") (class "Default")
      (node (ref "U1") (pin "4") (pinfunction "SCK/(~{INC})_4") (pintype "passive"))
      (node (ref "U4") (pin "4") (pinfunction "SCK/(~{INC})_4") (pintype "passive"))
    )
    (net (code "43") (name "unconnected-(U1-NC-Pad7)") (class "Default")
      (node (ref "U1") (pin "7") (pinfunction "NC_7") (pintype "passive"))
    )
    (net (code "44") (name "unconnected-(U1-NC-Pad8)") (class "Default")
      (node (ref "U1") (pin "8") (pinfunction "NC_8") (pintype "passive"))
    )
    (net (code "45") (name "unconnected-(U1-NC-Pad9)") (class "Default")
      (node (ref "U1") (pin "9") (pinfunction "NC_9") (pintype "passive"))
    )
    (net (code "46") (name "unconnected-(U1-NC-Pad13)") (class "Default")
      (node (ref "U1") (pin "13") (pinfunction "NC_13") (pintype "passive"))
    )
    (net (code "47") (name "unconnected-(U4-NC-Pad7)") (class "Default")
      (node (ref "U4") (pin "7") (pinfunction "NC_7") (pintype "passive"))
    )
    (net (code "48") (name "unconnected-(U4-NC-Pad8)") (class "Default")
      (node (ref "U4") (pin "8") (pinfunction "NC_8") (pintype "passive"))
    )
    (net (code "49") (name "unconnected-(U4-NC-Pad9)") (class "Default")
      (node (ref "U4") (pin "9") (pinfunction "NC_9") (pintype "passive"))
    )
    (net (code "50") (name "unconnected-(U4-NC-Pad13)") (class "Default")
      (node (ref "U4") (pin "13") (pinfunction "NC_13") (pintype "passive"))
    )
    (net (code "51") (name "unconnected-(U7-NC-Pad8)") (class "Default")
      (node (ref "U7") (pin "8") (pinfunction "NC_8") (pintype "passive"))
    )
    (net (code "52") (name "unconnected-(U7-NC-Pad9)") (class "Default")
      (node (ref "U7") (pin "9") (pinfunction "NC_9") (pintype "passive"))
    )
    (net (code "53") (name "unconnected-(U10-NC-Pad7)") (class "Default")
      (node (ref "U10") (pin "7") (pinfunction "NC_7") (pintype "passive"))
    )
    (net (code "54") (name "unconnected-(U10-NC-Pad8)") (class "Default")
      (node (ref "U10") (pin "8") (pinfunction "NC_8") (pintype "passive"))
    )
    (net (code "55") (name "unconnected-(U11-DIN(~{UD})-Pad5)") (class "Default")
      (node (ref "U11") (pin "5") (pinfunction "DIN(~{UD})_5") (pintype "passive"))
    )
    (net (code "56") (name "unconnected-(U11-NC-Pad7)") (class "Default")
      (node (ref "U11") (pin "7") (pinfunction "NC_7") (pintype "passive"))
    )
    (net (code "57") (name "unconnected-(U11-NC-Pad8)") (class "Default")
      (node (ref "U11") (pin "8") (pinfunction "NC_8") (pintype "passive"))
    )
    (net (code "58") (name "unconnected-(U11-NC-Pad9)") (class "Default")
      (node (ref "U11") (pin "9") (pinfunction "NC_9") (pintype "passive"))
    )
    (net (code "59") (name "unconnected-(U11-NC-Pad13)") (class "Default")
      (node (ref "U11") (pin "13") (pinfunction "NC_13") (pintype "passive"))
    )
    (net (code "60") (name "unconnected-(U11-SCK{slash}(~{INC})-Pad4)") (class "Default")
      (node (ref "U11") (pin "4") (pinfunction "SCK/(~{INC})_4") (pintype "passive"))
    )
    (net (code "61") (name "unconnected-(U11-SPI{slash}~{UD}-Pad6)") (class "Default")
      (node (ref "U11") (pin "6") (pinfunction "SPI/~{UD}_6") (pintype "passive"))
    )
    (net (code "62") (name "unconnected-(U11-~{CS}-Pad3)") (class "Default")
      (node (ref "U11") (pin "3") (pinfunction "~{CS}_3") (pintype "passive"))
    )
    (net (code "63") (name "unconnected-(U12-DIN(~{UD})-Pad5)") (class "Default")
      (node (ref "U12") (pin "5") (pinfunction "DIN(~{UD})_5") (pintype "passive"))
    )
    (net (code "64") (name "unconnected-(U12-NC-Pad7)") (class "Default")
      (node (ref "U12") (pin "7") (pinfunction "NC_7") (pintype "passive"))
    )
    (net (code "65") (name "unconnected-(U12-NC-Pad8)") (class "Default")
      (node (ref "U12") (pin "8") (pinfunction "NC_8") (pintype "passive"))
    )
    (net (code "66") (name "unconnected-(U12-NC-Pad9)") (class "Default")
      (node (ref "U12") (pin "9") (pinfunction "NC_9") (pintype "passive"))
    )
    (net (code "67") (name "unconnected-(U12-NC-Pad13)") (class "Default")
      (node (ref "U12") (pin "13") (pinfunction "NC_13") (pintype "passive"))
    )
    (net (code "68") (name "unconnected-(U12-SCK{slash}(~{INC})-Pad4)") (class "Default")
      (node (ref "U12") (pin "4") (pinfunction "SCK/(~{INC})_4") (pintype "passive"))
    )
    (net (code "69") (name "unconnected-(U12-SPI{slash}~{UD}-Pad6)") (class "Default")
      (node (ref "U12") (pin "6") (pinfunction "SPI/~{UD}_6") (pintype "passive"))
    )
    (net (code "70") (name "unconnected-(U12-~{CS}-Pad3)") (class "Default")
      (node (ref "U12") (pin "3") (pinfunction "~{CS}_3") (pintype "passive"))
    )
    (net (code "71") (name "unconnected-(U13-NC-Pad8)") (class "Default")
      (node (ref "U13") (pin "8") (pinfunction "NC_8") (pintype "passive"))
    )
    (net (code "72") (name "unconnected-(U13-NC-Pad9)") (class "Default")
      (node (ref "U13") (pin "9") (pinfunction "NC_9") (pintype "passive"))
    )
  )
)
